# sensor_to_uart.net
KiCad netlist of a schematic drawn in Altium Designer
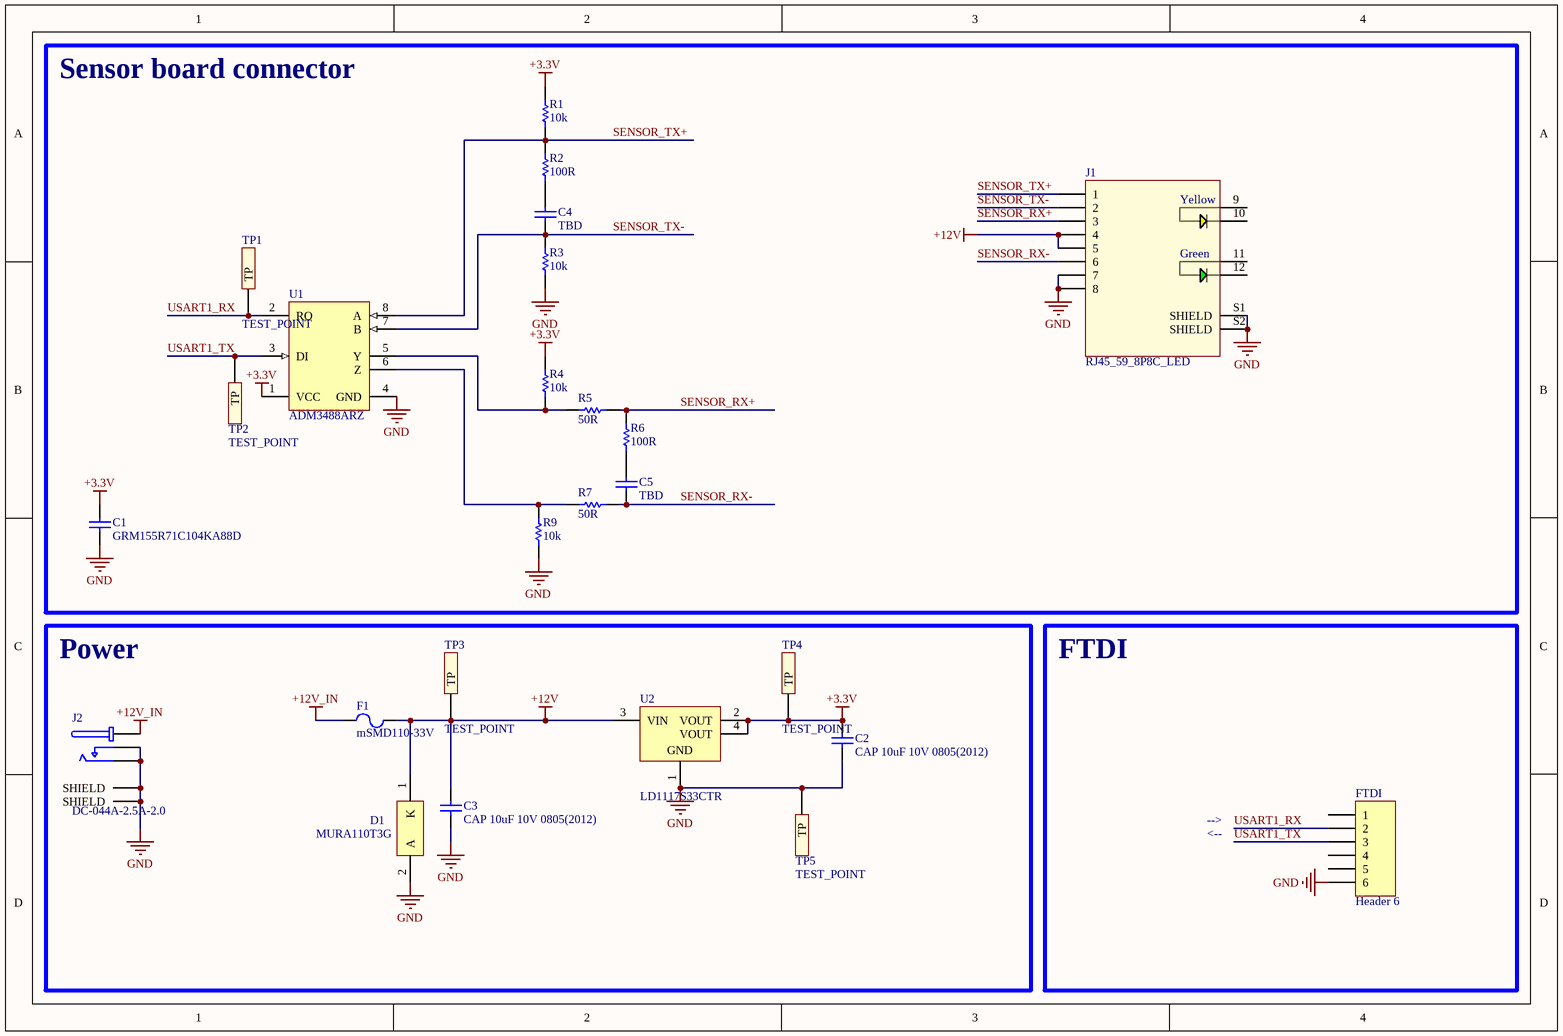
[diagram p0: sensor_to_uart.SchDoc]

(export (version "E")
  (design (tool "Eeschema 10.0.6"))
  (components
    (comp (ref "C1")
      (value "GRM155R71C104KA88D")
      (footprint "CAPC1005X55X25ML05T10")
      (description "Chip Capacitor, 0.1 uF, +/- 10%, 16 V, -55 to 125 degC, 0402 (1005 Metric), RoHS, Tape and Reel")
      (fields (field (name "VOLTAGE") "16V") (field (name "TOLERANCE") "10%"))
      (libsource (lib "Altium Content Vault") (part "CAP-NP-2"))
    )
    (comp (ref "C2")
      (value "CAP 10uF 10V 0805(2012)")
      (footprint "CAPC0805(2012)145_N")
      (description "CAP 10uF 10V ±10% 0805 (2012 Metric) Thickness 1.45mm SMD")
      (fields (field (name "TOLERANCE") "Â±10%"))
      (libsource (lib "Altium Content Vault") (part "CAP"))
    )
    (comp (ref "C3")
      (value "CAP 10uF 10V 0805(2012)")
      (footprint "CAPC0805(2012)145_N")
      (description "CAP 10uF 10V ±10% 0805 (2012 Metric) Thickness 1.45mm SMD")
      (fields (field (name "TOLERANCE") "Â±10%"))
      (libsource (lib "Altium Content Vault") (part "CAP"))
    )
    (comp (ref "C4")
      (value "TBD")
      (footprint "CAPC1005X55X25ML05T10")
      (description "Chip Capacitor, 0.1 uF, +/- 10%, 16 V, -55 to 125 degC, 0402 (1005 Metric), RoHS, Tape and Reel")
      (fields (field (name "VOLTAGE") "16V") (field (name "TOLERANCE") "10%"))
      (libsource (lib "Altium Content Vault") (part "CAP-NP-2"))
    )
    (comp (ref "C5")
      (value "TBD")
      (footprint "CAPC1005X55X25ML05T10")
      (description "Chip Capacitor, 0.1 uF, +/- 10%, 16 V, -55 to 125 degC, 0402 (1005 Metric), RoHS, Tape and Reel")
      (fields (field (name "VOLTAGE") "16V") (field (name "TOLERANCE") "10%"))
      (libsource (lib "Altium Content Vault") (part "CAP-NP-2"))
    )
    (comp (ref "D1")
      (value "MURA110T3G")
      (footprint "ONSC-SMA-2-403D-02_V")
      (description "Surface Mount Ultrafast Power Rectifier, 2-Pin SMA, Pb-Free, Tape and Reel")
      (fields (field (name "MANUFACTURER") "On Semiconductor"))
      (libsource (lib "Altium Content Vault") (part "ONSC-D-K1A2-2_A"))
    )
    (comp (ref "F1")
      (value "mSMD110-33V")
      (footprint "SEAANDLAND_1812")
      (description "Surface Mount Fuses 33V 100A 1.1A 2.2A 1812 RoHS")
      (fields (field (name "MANUFACTURER") "Sea & Land Electronic Corp"))
      (libsource (lib "Blinkinlabs") (part "mSMD110-33V"))
    )
    (comp (ref "FTDI")
      (value "Header 6")
      (footprint "HDR1X6")
      (description "Header, 6-Pin")
      (fields (field (name "PUBLISHER") "Altium Limited"))
      (libsource (lib "Miscellaneous Connectors") (part "Header 6"))
    )
    (comp (ref "J1")
      (value "RJ45_59_8P8C_LED")
      (footprint "RJ45_59_8P8C_LED")
      (description "Generic RJ49 jack with LED and without magnetics")
      (fields (field (name "MANUFACTURER") "Unknown/Generic"))
      (libsource (lib "Blinkinlabs") (part "RJ45_59_8P8C_LED"))
    )
    (comp (ref "J2")
      (value "DC-044A-2.5A-2.0")
      (footprint "DC-044A-2.5A-2.0")
      (description "DC Jack, 6mm OD, 2mm ID")
      (fields (field (name "MANUFACTURER") "XKB"))
      (libsource (lib "Blinkinlabs") (part "DC-044A-2.5A-2.0"))
    )
    (comp (ref "R1")
      (value "10k")
      (footprint "RESC0603(1608)_L")
      (description "120R 0.1W 5% 0603 (1608 Metric)  SMD")
      (fields (field (name "POWER") "0.1 W") (field (name "TOLERANCE") "5 %"))
      (libsource (lib "Altium Content Vault") (part "RES"))
    )
    (comp (ref "R2")
      (value "100R")
      (footprint "RESC0603(1608)_L")
      (description "120R 0.1W 5% 0603 (1608 Metric)  SMD")
      (fields (field (name "POWER") "0.1 W") (field (name "TOLERANCE") "5 %"))
      (libsource (lib "Altium Content Vault") (part "RES"))
    )
    (comp (ref "R3")
      (value "10k")
      (footprint "RESC0603(1608)_L")
      (description "120R 0.1W 5% 0603 (1608 Metric)  SMD")
      (fields (field (name "POWER") "0.1 W") (field (name "TOLERANCE") "5 %"))
      (libsource (lib "Altium Content Vault") (part "RES"))
    )
    (comp (ref "R4")
      (value "10k")
      (footprint "RESC0603(1608)_L")
      (description "120R 0.1W 5% 0603 (1608 Metric)  SMD")
      (fields (field (name "POWER") "0.1 W") (field (name "TOLERANCE") "5 %"))
      (libsource (lib "Altium Content Vault") (part "RES"))
    )
    (comp (ref "R5")
      (value "50R")
      (footprint "RESC0603(1608)_L")
      (description "120R 0.1W 5% 0603 (1608 Metric)  SMD")
      (fields (field (name "POWER") "0.1 W") (field (name "TOLERANCE") "5 %"))
      (libsource (lib "Altium Content Vault") (part "RES"))
    )
    (comp (ref "R6")
      (value "100R")
      (footprint "RESC0603(1608)_L")
      (description "120R 0.1W 5% 0603 (1608 Metric)  SMD")
      (fields (field (name "POWER") "0.1 W") (field (name "TOLERANCE") "5 %"))
      (libsource (lib "Altium Content Vault") (part "RES"))
    )
    (comp (ref "R7")
      (value "50R")
      (footprint "RESC0603(1608)_L")
      (description "120R 0.1W 5% 0603 (1608 Metric)  SMD")
      (fields (field (name "POWER") "0.1 W") (field (name "TOLERANCE") "5 %"))
      (libsource (lib "Altium Content Vault") (part "RES"))
    )
    (comp (ref "R9")
      (value "10k")
      (footprint "RESC0603(1608)_L")
      (description "120R 0.1W 5% 0603 (1608 Metric)  SMD")
      (fields (field (name "POWER") "0.1 W") (field (name "TOLERANCE") "5 %"))
      (libsource (lib "Altium Content Vault") (part "RES"))
    )
    (comp (ref "TP1")
      (value "TEST_POINT")
      (footprint "TP-SMD-1mm")
      (description "Test point")
      (libsource (lib "") (part "TEST_POINT_1"))
    )
    (comp (ref "TP2")
      (value "TEST_POINT")
      (footprint "TP-SMD-1mm")
      (description "Test point")
      (libsource (lib "Blinkinlabs") (part "TEST_POINT"))
    )
    (comp (ref "TP3")
      (value "TEST_POINT")
      (footprint "TP-SMD-1mm")
      (description "Test point")
      (libsource (lib "") (part "TEST_POINT_1"))
    )
    (comp (ref "TP4")
      (value "TEST_POINT")
      (footprint "TP-SMD-1mm")
      (description "Test point")
      (libsource (lib "") (part "TEST_POINT_1"))
    )
    (comp (ref "TP5")
      (value "TEST_POINT")
      (footprint "TP-SMD-1mm")
      (description "Test point")
      (libsource (lib "Blinkinlabs") (part "TEST_POINT"))
    )
    (comp (ref "U1")
      (value "ADM3488ARZ")
      (footprint "ADI-R-8_L")
      (fields (field (name "MANUFACTURER") "Analog Devices"))
      (libsource (lib "Altium Content Vault") (part "ADI-ADM3488_90-R-8"))
    )
    (comp (ref "U2")
      (value "LD1117S33CTR")
      (footprint "SOT-223_N")
      (description "Fixed Low Drop Positive Voltage Regulator, 3.3V, 4-Pin SOT-223, Tape and Reel")
      (libsource (lib "Altium Content Vault") (part "PM-REG-LD1117-SOT4"))
    )
  )
  (nets
    (net (code "1") (name "+3.3V") (class "Default")
      (node (ref "C1") (pin "2") (pinfunction "2_2") (pintype "passive"))
      (node (ref "C2") (pin "2") (pinfunction "2_2") (pintype "passive"))
      (node (ref "R1") (pin "1") (pinfunction "1_1") (pintype "passive"))
      (node (ref "R4") (pin "1") (pinfunction "1_1") (pintype "passive"))
      (node (ref "TP4") (pin "1") (pinfunction "TP_1") (pintype "passive"))
      (node (ref "U1") (pin "1") (pinfunction "VCC_1") (pintype "power_in"))
      (node (ref "U2") (pin "2") (pinfunction "VOUT_2") (pintype "power_in"))
      (node (ref "U2") (pin "4") (pinfunction "VOUT_4") (pintype "power_in"))
    )
    (net (code "2") (name "+12V") (class "Default")
      (node (ref "C3") (pin "2") (pinfunction "2_2") (pintype "passive"))
      (node (ref "D1") (pin "1") (pinfunction "K_1") (pintype "passive"))
      (node (ref "F1") (pin "2") (pinfunction "2_2") (pintype "passive"))
      (node (ref "J1") (pin "4") (pinfunction "4_4") (pintype "passive"))
      (node (ref "J1") (pin "5") (pinfunction "5_5") (pintype "passive"))
      (node (ref "TP3") (pin "1") (pinfunction "TP_1") (pintype "passive"))
      (node (ref "U2") (pin "3") (pinfunction "VIN_3") (pintype "power_in"))
    )
    (net (code "3") (name "+12V_IN") (class "Default")
      (node (ref "F1") (pin "1") (pinfunction "1_1") (pintype "passive"))
      (node (ref "J2") (pin "1") (pinfunction "1_1") (pintype "passive"))
    )
    (net (code "4") (name "/SENSOR_RX+") (class "Default")
      (node (ref "J1") (pin "3") (pinfunction "3_3") (pintype "passive"))
      (node (ref "R5") (pin "1") (pinfunction "1_1") (pintype "passive"))
      (node (ref "R6") (pin "1") (pinfunction "1_1") (pintype "passive"))
    )
    (net (code "5") (name "/SENSOR_RX-") (class "Default")
      (node (ref "C5") (pin "1") (pinfunction "1_1") (pintype "passive"))
      (node (ref "J1") (pin "6") (pinfunction "6_6") (pintype "passive"))
      (node (ref "R7") (pin "1") (pinfunction "1_1") (pintype "passive"))
    )
    (net (code "6") (name "/SENSOR_TX+") (class "Default")
      (node (ref "J1") (pin "1") (pinfunction "1_1") (pintype "passive"))
      (node (ref "R1") (pin "2") (pinfunction "2_2") (pintype "passive"))
      (node (ref "R2") (pin "1") (pinfunction "1_1") (pintype "passive"))
      (node (ref "U1") (pin "8") (pinfunction "A_8") (pintype "input"))
    )
    (net (code "7") (name "/SENSOR_TX-") (class "Default")
      (node (ref "C4") (pin "1") (pinfunction "1_1") (pintype "passive"))
      (node (ref "J1") (pin "2") (pinfunction "2_2") (pintype "passive"))
      (node (ref "R3") (pin "1") (pinfunction "1_1") (pintype "passive"))
      (node (ref "U1") (pin "7") (pinfunction "B_7") (pintype "input"))
    )
    (net (code "8") (name "/USART1_RX") (class "Default")
      (node (ref "FTDI") (pin "2") (pinfunction "2_2") (pintype "passive"))
      (node (ref "TP1") (pin "1") (pinfunction "TP_1") (pintype "passive"))
      (node (ref "U1") (pin "2") (pinfunction "RO_2") (pintype "tri_state"))
    )
    (net (code "9") (name "/USART1_TX") (class "Default")
      (node (ref "FTDI") (pin "3") (pinfunction "3_3") (pintype "passive"))
      (node (ref "TP2") (pin "1") (pinfunction "TP_1") (pintype "passive"))
      (node (ref "U1") (pin "3") (pinfunction "DI_3") (pintype "input"))
    )
    (net (code "10") (name "GND") (class "Default")
      (node (ref "C1") (pin "1") (pinfunction "1_1") (pintype "passive"))
      (node (ref "C2") (pin "1") (pinfunction "1_1") (pintype "passive"))
      (node (ref "C3") (pin "1") (pinfunction "1_1") (pintype "passive"))
      (node (ref "D1") (pin "2") (pinfunction "A_2") (pintype "passive"))
      (node (ref "FTDI") (pin "6") (pinfunction "6_6") (pintype "passive"))
      (node (ref "J1") (pin "7") (pinfunction "7_7") (pintype "passive"))
      (node (ref "J1") (pin "8") (pinfunction "8_8") (pintype "passive"))
      (node (ref "J1") (pin "S1") (pinfunction "SHIELD_S1") (pintype "passive"))
      (node (ref "J1") (pin "S2") (pinfunction "SHIELD_S2") (pintype "passive"))
      (node (ref "J2") (pin "2") (pinfunction "2_2") (pintype "passive"))
      (node (ref "J2") (pin "3") (pinfunction "3_3") (pintype "passive"))
      (node (ref "J2") (pin "4") (pinfunction "SHIELD_4") (pintype "passive"))
      (node (ref "J2") (pin "5") (pinfunction "SHIELD_5") (pintype "passive"))
      (node (ref "R3") (pin "2") (pinfunction "2_2") (pintype "passive"))
      (node (ref "R9") (pin "2") (pinfunction "2_2") (pintype "passive"))
      (node (ref "TP5") (pin "1") (pinfunction "TP_1") (pintype "passive"))
      (node (ref "U1") (pin "4") (pinfunction "GND_4") (pintype "power_in"))
      (node (ref "U2") (pin "1") (pinfunction "GND_1") (pintype "power_in"))
    )
    (net (code "11") (name "Net-(C4-Pad2)") (class "Default")
      (node (ref "C4") (pin "2") (pinfunction "2_2") (pintype "passive"))
      (node (ref "R2") (pin "2") (pinfunction "2_2") (pintype "passive"))
    )
    (net (code "12") (name "Net-(C5-Pad2)") (class "Default")
      (node (ref "C5") (pin "2") (pinfunction "2_2") (pintype "passive"))
      (node (ref "R6") (pin "2") (pinfunction "2_2") (pintype "passive"))
    )
    (net (code "13") (name "Net-(U1-Y)") (class "Default")
      (node (ref "R4") (pin "2") (pinfunction "2_2") (pintype "passive"))
      (node (ref "R5") (pin "2") (pinfunction "2_2") (pintype "passive"))
      (node (ref "U1") (pin "5") (pinfunction "Y_5") (pintype "tri_state"))
    )
    (net (code "14") (name "Net-(U1-Z)") (class "Default")
      (node (ref "R7") (pin "2") (pinfunction "2_2") (pintype "passive"))
      (node (ref "R9") (pin "1") (pinfunction "1_1") (pintype "passive"))
      (node (ref "U1") (pin "6") (pinfunction "Z_6") (pintype "tri_state"))
    )
    (net (code "15") (name "unconnected-(FTDI-Pad1)") (class "Default")
      (node (ref "FTDI") (pin "1") (pinfunction "1_1") (pintype "passive"))
    )
    (net (code "16") (name "unconnected-(FTDI-Pad4)") (class "Default")
      (node (ref "FTDI") (pin "4") (pinfunction "4_4") (pintype "passive"))
    )
    (net (code "17") (name "unconnected-(FTDI-Pad5)") (class "Default")
      (node (ref "FTDI") (pin "5") (pinfunction "5_5") (pintype "passive"))
    )
    (net (code "18") (name "unconnected-(J1-Green_Anode-Pad11)") (class "Default")
      (node (ref "J1") (pin "11") (pinfunction "Green_Anode_11") (pintype "passive"))
    )
    (net (code "19") (name "unconnected-(J1-Green_Cathode-Pad12)") (class "Default")
      (node (ref "J1") (pin "12") (pinfunction "Green_Cathode_12") (pintype "passive"))
    )
    (net (code "20") (name "unconnected-(J1-Yellow_Anode-Pad9)") (class "Default")
      (node (ref "J1") (pin "9") (pinfunction "Yellow_Anode_9") (pintype "passive"))
    )
    (net (code "21") (name "unconnected-(J1-Yellow_Cathode-Pad10)") (class "Default")
      (node (ref "J1") (pin "10") (pinfunction "Yellow_Cathode_10") (pintype "passive"))
    )
  )
)
